# SolderDispenser_v1_2.net
KiCad netlist of a schematic drawn in EAGLE
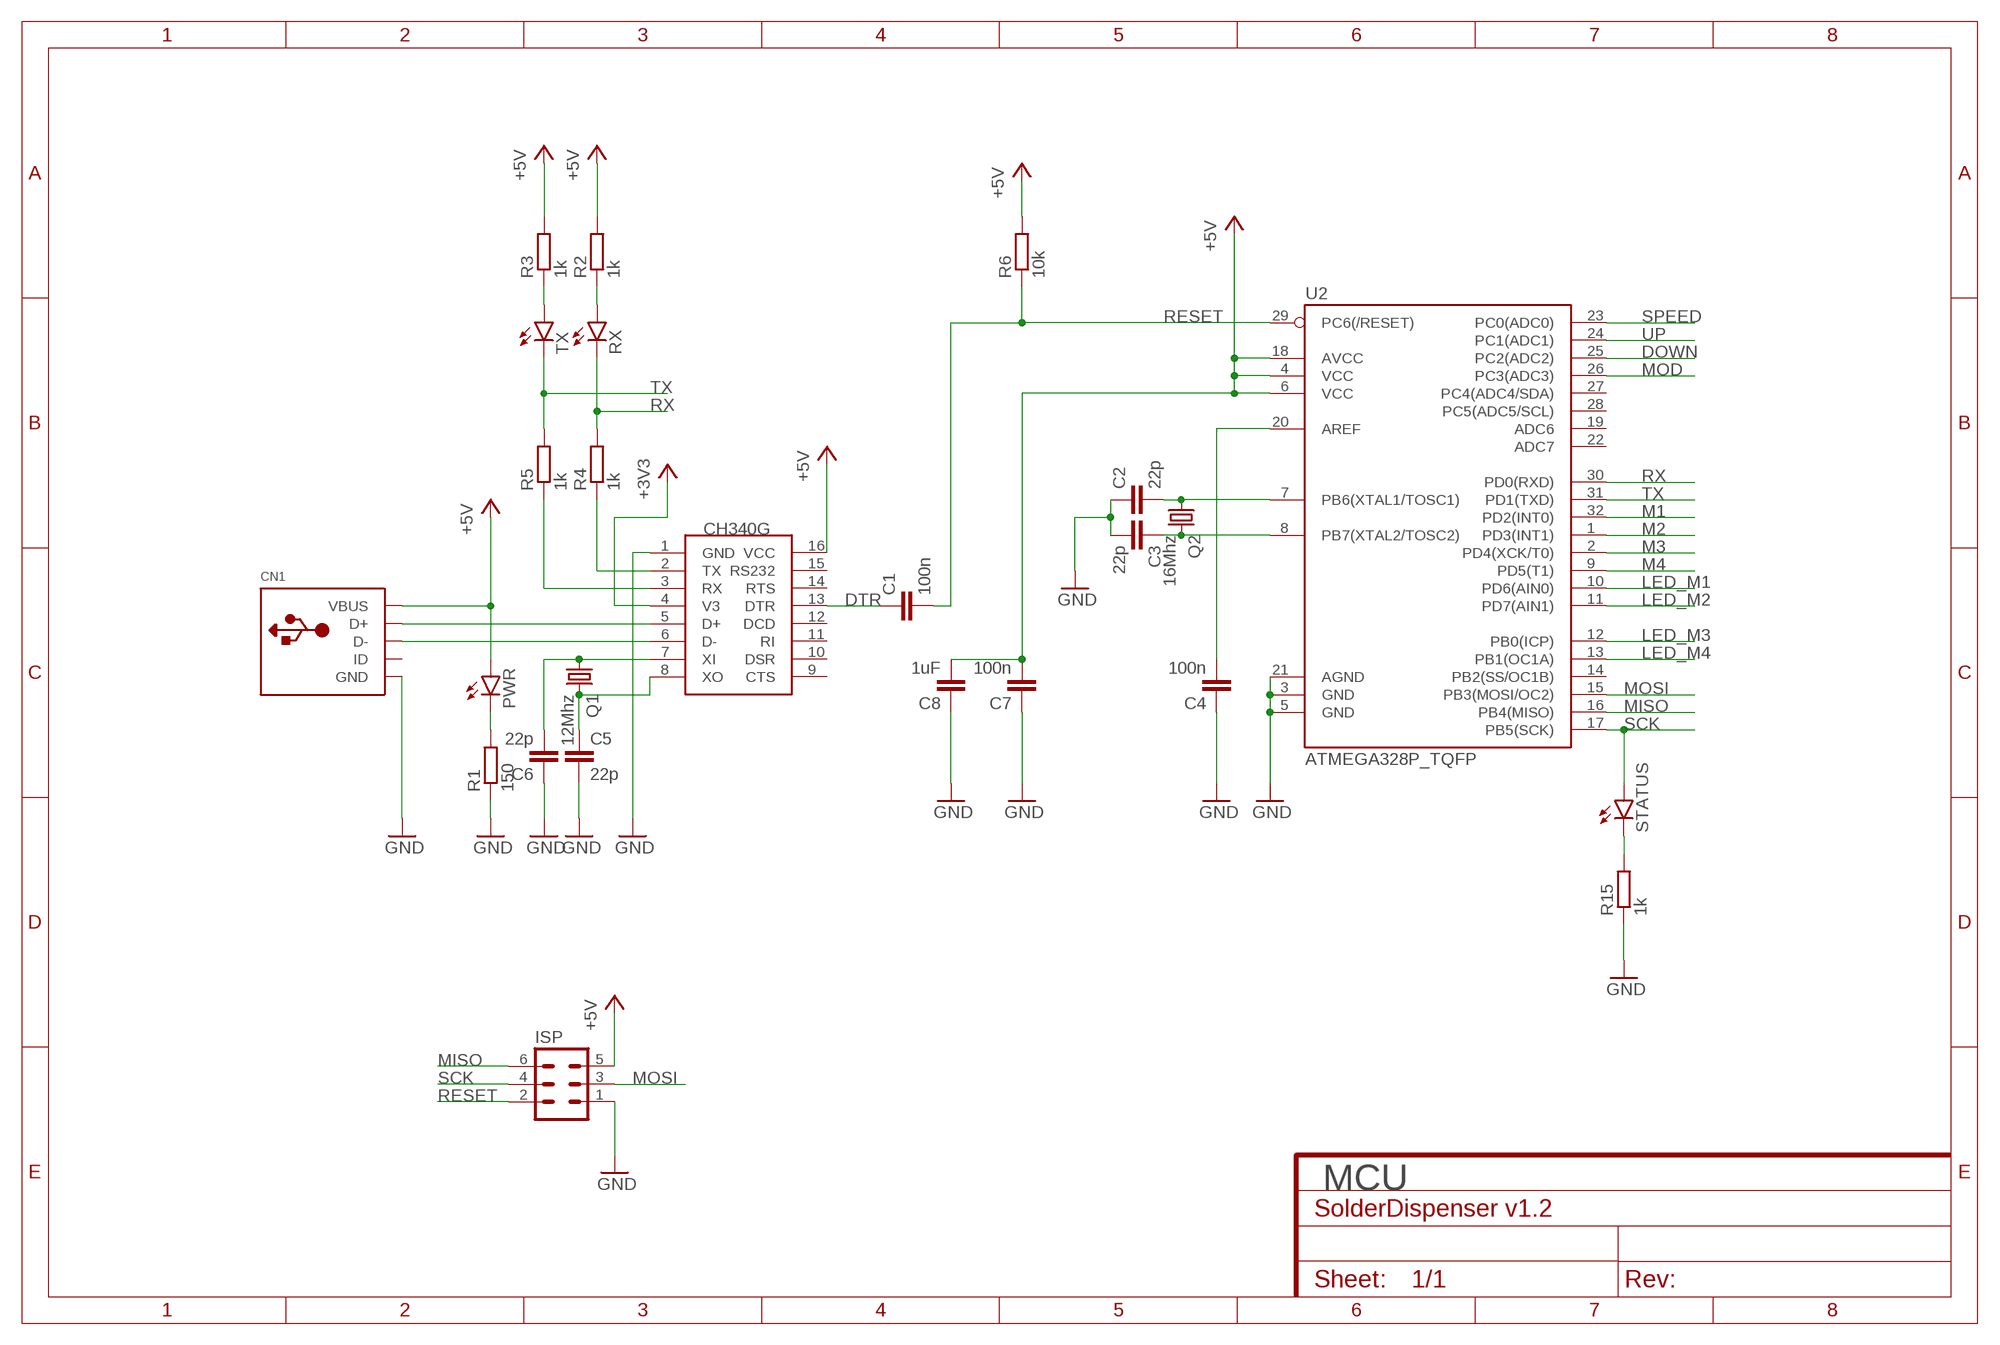
[diagram p0: schematic, sheet 1, part 1 of 2]
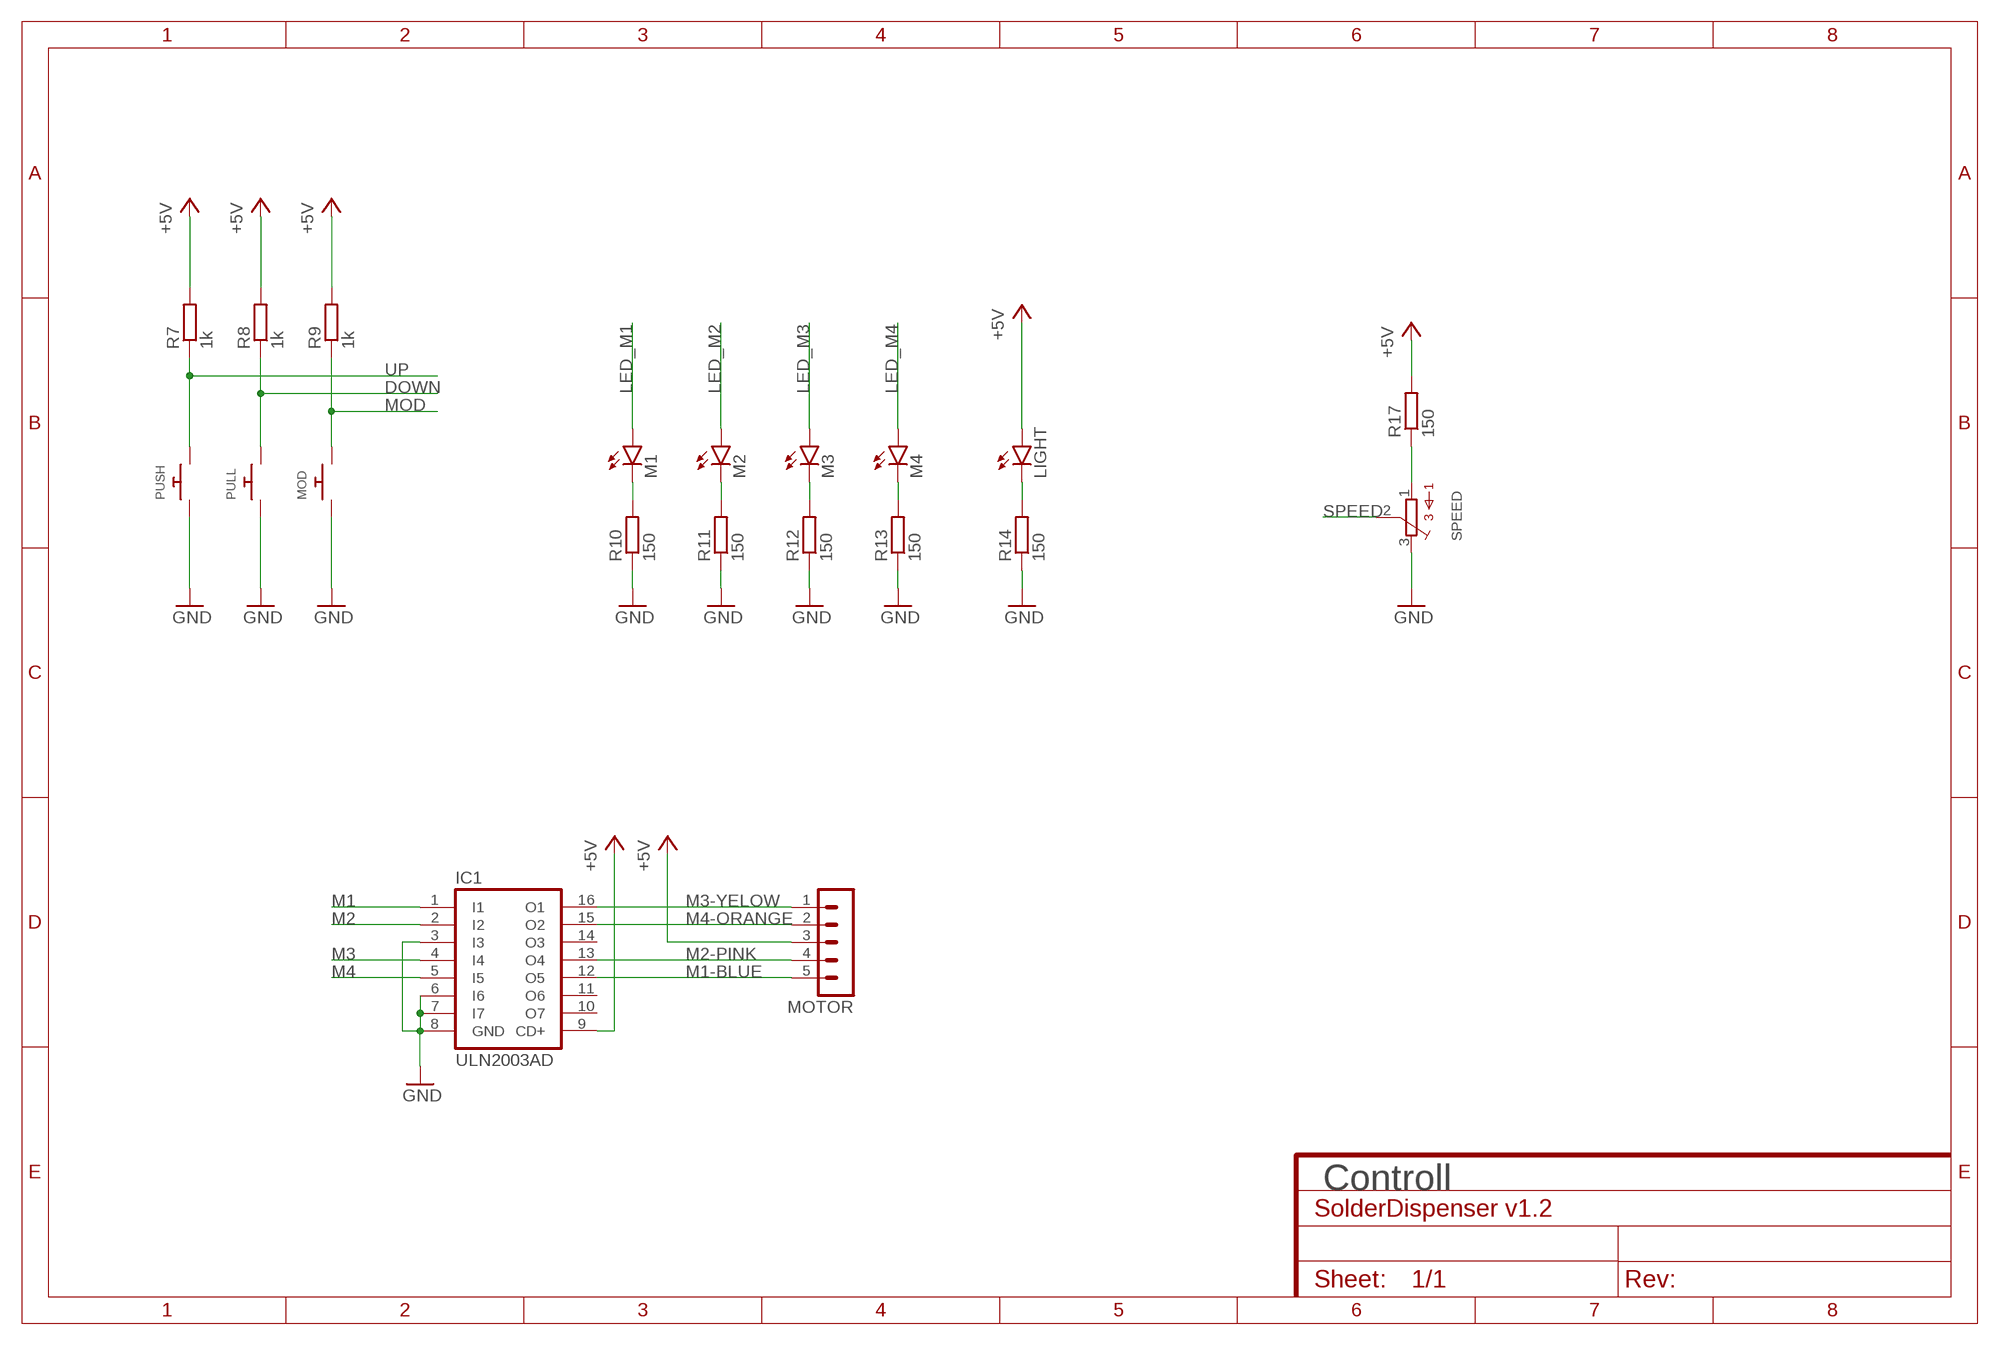
[diagram p1: schematic, sheet 1, part 2 of 2]

(export (version "E")
  (design (tool "Eeschema 10.0.6"))
  (components
    (comp (ref "C1")
      (value "100n")
      (footprint "eagle-import:C0805")
      (libsource (lib "eagle-import") (part "C-EUC0805"))
    )
    (comp (ref "C2")
      (value "22p")
      (footprint "eagle-import:C0805")
      (libsource (lib "eagle-import") (part "C-EUC0805"))
    )
    (comp (ref "C3")
      (value "22p")
      (footprint "eagle-import:C0805")
      (libsource (lib "eagle-import") (part "C-EUC0805"))
    )
    (comp (ref "C4")
      (value "100n")
      (footprint "eagle-import:C0805")
      (libsource (lib "eagle-import") (part "C-EUC0805"))
    )
    (comp (ref "C5")
      (value "22p")
      (footprint "eagle-import:C0805")
      (libsource (lib "eagle-import") (part "C-EUC0805"))
    )
    (comp (ref "C6")
      (value "22p")
      (footprint "eagle-import:C0805")
      (libsource (lib "eagle-import") (part "C-EUC0805"))
    )
    (comp (ref "C7")
      (value "100n")
      (footprint "eagle-import:C0805")
      (libsource (lib "eagle-import") (part "C-EUC0805"))
    )
    (comp (ref "C8")
      (value "1uF")
      (footprint "eagle-import:C0805")
      (libsource (lib "eagle-import") (part "C-EUC0805"))
    )
    (comp (ref "CN1")
      (value "USBMOLEX")
      (footprint "eagle-import:USB-MINIB-THM-MOLEX")
      (libsource (lib "eagle-import") (part "USBMOLEX"))
    )
    (comp (ref "IC1")
      (value "ULN2003AD")
      (footprint "eagle-import:SO16")
      (libsource (lib "eagle-import") (part "ULN2003AD"))
    )
    (comp (ref "ISP")
      (value "MA03-2")
      (footprint "eagle-import:MA03-2")
      (libsource (lib "eagle-import") (part "MA03-2"))
    )
    (comp (ref "LIGHT")
      (value "LED5MM")
      (footprint "eagle-import:LED5MM")
      (libsource (lib "eagle-import") (part "LED5MM"))
    )
    (comp (ref "M1")
      (value "LEDSML0805")
      (footprint "eagle-import:SML0805")
      (libsource (lib "eagle-import") (part "LEDSML0805"))
    )
    (comp (ref "M2")
      (value "LEDSML0805")
      (footprint "eagle-import:SML0805")
      (libsource (lib "eagle-import") (part "LEDSML0805"))
    )
    (comp (ref "M3")
      (value "LEDSML0805")
      (footprint "eagle-import:SML0805")
      (libsource (lib "eagle-import") (part "LEDSML0805"))
    )
    (comp (ref "M4")
      (value "LEDSML0805")
      (footprint "eagle-import:SML0805")
      (libsource (lib "eagle-import") (part "LEDSML0805"))
    )
    (comp (ref "MOD")
      (value "SWITCH_PUSHBUTTONEVQ-PE")
      (footprint "eagle-import:TACT_PANA-EVQ")
      (libsource (lib "eagle-import") (part "SWITCH_PUSHBUTTONEVQ-PE"))
    )
    (comp (ref "MOTOR")
      (value "MA05-1")
      (footprint "eagle-import:MA05-1")
      (libsource (lib "eagle-import") (part "MA05-1"))
    )
    (comp (ref "PULL")
      (value "SWITCH_PUSHBUTTONEVQ-PE")
      (footprint "eagle-import:TACT_PANA-EVQ")
      (libsource (lib "eagle-import") (part "SWITCH_PUSHBUTTONEVQ-PE"))
    )
    (comp (ref "PUSH")
      (value "SWITCH_PUSHBUTTONEVQ-PE")
      (footprint "eagle-import:TACT_PANA-EVQ")
      (libsource (lib "eagle-import") (part "SWITCH_PUSHBUTTONEVQ-PE"))
    )
    (comp (ref "PWR")
      (value "LEDSML0805")
      (footprint "eagle-import:SML0805")
      (libsource (lib "eagle-import") (part "LEDSML0805"))
    )
    (comp (ref "Q1")
      (value "12Mhz")
      (footprint "eagle-import:HC49UP")
      (libsource (lib "eagle-import") (part "CRYSTALHC49UP"))
    )
    (comp (ref "Q2")
      (value "16Mhz")
      (footprint "eagle-import:HC49UP")
      (libsource (lib "eagle-import") (part "CRYSTALHC49UP"))
    )
    (comp (ref "R1")
      (value "150")
      (footprint "eagle-import:R0805")
      (libsource (lib "eagle-import") (part "R-EU_R0805"))
    )
    (comp (ref "R2")
      (value "1k")
      (footprint "eagle-import:R0805")
      (libsource (lib "eagle-import") (part "R-EU_R0805"))
    )
    (comp (ref "R3")
      (value "1k")
      (footprint "eagle-import:R0805")
      (libsource (lib "eagle-import") (part "R-EU_R0805"))
    )
    (comp (ref "R4")
      (value "1k")
      (footprint "eagle-import:R0805")
      (libsource (lib "eagle-import") (part "R-EU_R0805"))
    )
    (comp (ref "R5")
      (value "1k")
      (footprint "eagle-import:R0805")
      (libsource (lib "eagle-import") (part "R-EU_R0805"))
    )
    (comp (ref "R6")
      (value "10k")
      (footprint "eagle-import:R0805")
      (libsource (lib "eagle-import") (part "R-EU_R0805"))
    )
    (comp (ref "R7")
      (value "1k")
      (footprint "eagle-import:R0805")
      (libsource (lib "eagle-import") (part "R-EU_R0805"))
    )
    (comp (ref "R8")
      (value "1k")
      (footprint "eagle-import:R0805")
      (libsource (lib "eagle-import") (part "R-EU_R0805"))
    )
    (comp (ref "R9")
      (value "1k")
      (footprint "eagle-import:R0805")
      (libsource (lib "eagle-import") (part "R-EU_R0805"))
    )
    (comp (ref "R10")
      (value "150")
      (footprint "eagle-import:R0805")
      (libsource (lib "eagle-import") (part "R-EU_R0805"))
    )
    (comp (ref "R11")
      (value "150")
      (footprint "eagle-import:R0805")
      (libsource (lib "eagle-import") (part "R-EU_R0805"))
    )
    (comp (ref "R12")
      (value "150")
      (footprint "eagle-import:R0805")
      (libsource (lib "eagle-import") (part "R-EU_R0805"))
    )
    (comp (ref "R13")
      (value "150")
      (footprint "eagle-import:R0805")
      (libsource (lib "eagle-import") (part "R-EU_R0805"))
    )
    (comp (ref "R14")
      (value "150")
      (footprint "eagle-import:R0805")
      (libsource (lib "eagle-import") (part "R-EU_R0805"))
    )
    (comp (ref "R15")
      (value "1k")
      (footprint "eagle-import:R0805")
      (libsource (lib "eagle-import") (part "R-EU_R0805"))
    )
    (comp (ref "R17")
      (value "150")
      (footprint "eagle-import:R0805")
      (libsource (lib "eagle-import") (part "R-EU_R0805"))
    )
    (comp (ref "RX")
      (value "LEDSML0805")
      (footprint "eagle-import:SML0805")
      (libsource (lib "eagle-import") (part "LEDSML0805"))
    )
    (comp (ref "SPEED")
      (value "3362P")
      (footprint "eagle-import:3362P")
      (libsource (lib "eagle-import") (part "3362P"))
    )
    (comp (ref "STATUS")
      (value "LEDSML0805")
      (footprint "eagle-import:SML0805")
      (libsource (lib "eagle-import") (part "LEDSML0805"))
    )
    (comp (ref "TX")
      (value "LEDSML0805")
      (footprint "eagle-import:SML0805")
      (libsource (lib "eagle-import") (part "LEDSML0805"))
    )
    (comp (ref "U$1")
      (value "CH340G")
      (footprint "eagle-import:SOIC16")
      (libsource (lib "eagle-import") (part "CH340G"))
    )
    (comp (ref "U2")
      (value "ATMEGA328P_TQFP")
      (footprint "eagle-import:TQFP32-08")
      (libsource (lib "eagle-import") (part "ATMEGA328P_TQFP"))
    )
  )
  (nets
    (net (code "1") (name "+3V3") (class "Default")
      (node (ref "U$1") (pin "4") (pinfunction "V3_4") (pintype "bidirectional"))
    )
    (net (code "2") (name "+5V") (class "Default")
      (node (ref "C7") (pin "2") (pinfunction "2_2") (pintype "passive"))
      (node (ref "C8") (pin "2") (pinfunction "2_2") (pintype "passive"))
      (node (ref "CN1") (pin "VBUS") (pinfunction "VBUS_VBUS") (pintype "power_in"))
      (node (ref "IC1") (pin "9") (pinfunction "CD+_9") (pintype "passive"))
      (node (ref "ISP") (pin "5") (pinfunction "5_5") (pintype "passive"))
      (node (ref "LIGHT") (pin "A") (pinfunction "A_A") (pintype "passive"))
      (node (ref "MOTOR") (pin "3") (pinfunction "3_3") (pintype "passive"))
      (node (ref "PWR") (pin "A") (pinfunction "A_A") (pintype "passive"))
      (node (ref "R17") (pin "2") (pinfunction "2_2") (pintype "passive"))
      (node (ref "R2") (pin "2") (pinfunction "2_2") (pintype "passive"))
      (node (ref "R3") (pin "2") (pinfunction "2_2") (pintype "passive"))
      (node (ref "R6") (pin "2") (pinfunction "2_2") (pintype "passive"))
      (node (ref "R7") (pin "2") (pinfunction "2_2") (pintype "passive"))
      (node (ref "R8") (pin "2") (pinfunction "2_2") (pintype "passive"))
      (node (ref "R9") (pin "2") (pinfunction "2_2") (pintype "passive"))
      (node (ref "U$1") (pin "16") (pinfunction "VCC_16") (pintype "bidirectional"))
      (node (ref "U2") (pin "18") (pinfunction "AVCC_18") (pintype "bidirectional"))
      (node (ref "U2") (pin "4") (pinfunction "VCC_4") (pintype "bidirectional"))
      (node (ref "U2") (pin "6") (pinfunction "VCC_6") (pintype "bidirectional"))
    )
    (net (code "3") (name "/DOWN") (class "Default")
      (node (ref "PULL") (pin "P$2") (pinfunction "P$2_P$2") (pintype "passive"))
      (node (ref "R8") (pin "1") (pinfunction "1_1") (pintype "passive"))
      (node (ref "U2") (pin "25") (pinfunction "PC2(ADC2)_25") (pintype "bidirectional"))
    )
    (net (code "4") (name "/DTR") (class "Default")
      (node (ref "C1") (pin "1") (pinfunction "1_1") (pintype "passive"))
      (node (ref "U$1") (pin "13") (pinfunction "DTR_13") (pintype "bidirectional"))
    )
    (net (code "5") (name "/LED_M1") (class "Default")
      (node (ref "M1") (pin "A") (pinfunction "A_A") (pintype "passive"))
      (node (ref "U2") (pin "10") (pinfunction "PD6(AIN0)_10") (pintype "bidirectional"))
    )
    (net (code "6") (name "/LED_M2") (class "Default")
      (node (ref "M2") (pin "A") (pinfunction "A_A") (pintype "passive"))
      (node (ref "U2") (pin "11") (pinfunction "PD7(AIN1)_11") (pintype "bidirectional"))
    )
    (net (code "7") (name "/LED_M3") (class "Default")
      (node (ref "M3") (pin "A") (pinfunction "A_A") (pintype "passive"))
      (node (ref "U2") (pin "12") (pinfunction "PB0(ICP)_12") (pintype "bidirectional"))
    )
    (net (code "8") (name "/LED_M4") (class "Default")
      (node (ref "M4") (pin "A") (pinfunction "A_A") (pintype "passive"))
      (node (ref "U2") (pin "13") (pinfunction "PB1(OC1A)_13") (pintype "bidirectional"))
    )
    (net (code "9") (name "/M1") (class "Default")
      (node (ref "IC1") (pin "1") (pinfunction "I1_1") (pintype "input"))
      (node (ref "U2") (pin "32") (pinfunction "PD2(INT0)_32") (pintype "bidirectional"))
    )
    (net (code "10") (name "/M1-BLUE") (class "Default")
      (node (ref "IC1") (pin "12") (pinfunction "O5_12") (pintype "open_collector"))
      (node (ref "MOTOR") (pin "5") (pinfunction "5_5") (pintype "passive"))
    )
    (net (code "11") (name "/M2") (class "Default")
      (node (ref "IC1") (pin "2") (pinfunction "I2_2") (pintype "input"))
      (node (ref "U2") (pin "1") (pinfunction "PD3(INT1)_1") (pintype "bidirectional"))
    )
    (net (code "12") (name "/M2-PINK") (class "Default")
      (node (ref "IC1") (pin "13") (pinfunction "O4_13") (pintype "open_collector"))
      (node (ref "MOTOR") (pin "4") (pinfunction "4_4") (pintype "passive"))
    )
    (net (code "13") (name "/M3") (class "Default")
      (node (ref "IC1") (pin "4") (pinfunction "I4_4") (pintype "input"))
      (node (ref "U2") (pin "2") (pinfunction "PD4(XCK/T0)_2") (pintype "bidirectional"))
    )
    (net (code "14") (name "/M3-YELOW") (class "Default")
      (node (ref "IC1") (pin "16") (pinfunction "O1_16") (pintype "open_collector"))
      (node (ref "MOTOR") (pin "1") (pinfunction "1_1") (pintype "passive"))
    )
    (net (code "15") (name "/M4") (class "Default")
      (node (ref "IC1") (pin "5") (pinfunction "I5_5") (pintype "input"))
      (node (ref "U2") (pin "9") (pinfunction "PD5(T1)_9") (pintype "bidirectional"))
    )
    (net (code "16") (name "/M4-ORANGE") (class "Default")
      (node (ref "IC1") (pin "15") (pinfunction "O2_15") (pintype "open_collector"))
      (node (ref "MOTOR") (pin "2") (pinfunction "2_2") (pintype "passive"))
    )
    (net (code "17") (name "/MISO") (class "Default")
      (node (ref "ISP") (pin "6") (pinfunction "6_6") (pintype "passive"))
      (node (ref "U2") (pin "16") (pinfunction "PB4(MISO)_16") (pintype "bidirectional"))
    )
    (net (code "18") (name "/MOD") (class "Default")
      (node (ref "MOD") (pin "P$2") (pinfunction "P$2_P$2") (pintype "passive"))
      (node (ref "R9") (pin "1") (pinfunction "1_1") (pintype "passive"))
      (node (ref "U2") (pin "26") (pinfunction "PC3(ADC3)_26") (pintype "bidirectional"))
    )
    (net (code "19") (name "/MOSI") (class "Default")
      (node (ref "ISP") (pin "3") (pinfunction "3_3") (pintype "passive"))
      (node (ref "U2") (pin "15") (pinfunction "PB3(MOSI/OC2)_15") (pintype "bidirectional"))
    )
    (net (code "20") (name "/RESET") (class "Default")
      (node (ref "C1") (pin "2") (pinfunction "2_2") (pintype "passive"))
      (node (ref "ISP") (pin "2") (pinfunction "2_2") (pintype "passive"))
      (node (ref "R6") (pin "1") (pinfunction "1_1") (pintype "passive"))
      (node (ref "U2") (pin "29") (pinfunction "PC6(/RESET)_29") (pintype "bidirectional"))
    )
    (net (code "21") (name "/RX") (class "Default")
      (node (ref "R4") (pin "2") (pinfunction "2_2") (pintype "passive"))
      (node (ref "RX") (pin "C") (pinfunction "C_C") (pintype "passive"))
      (node (ref "U2") (pin "30") (pinfunction "PD0(RXD)_30") (pintype "bidirectional"))
    )
    (net (code "22") (name "/SCK") (class "Default")
      (node (ref "ISP") (pin "4") (pinfunction "4_4") (pintype "passive"))
      (node (ref "STATUS") (pin "A") (pinfunction "A_A") (pintype "passive"))
      (node (ref "U2") (pin "17") (pinfunction "PB5(SCK)_17") (pintype "bidirectional"))
    )
    (net (code "23") (name "/SPEED") (class "Default")
      (node (ref "SPEED") (pin "2") (pinfunction "2_2") (pintype "passive"))
      (node (ref "U2") (pin "23") (pinfunction "PC0(ADC0)_23") (pintype "bidirectional"))
    )
    (net (code "24") (name "/TX") (class "Default")
      (node (ref "R5") (pin "2") (pinfunction "2_2") (pintype "passive"))
      (node (ref "TX") (pin "C") (pinfunction "C_C") (pintype "passive"))
      (node (ref "U2") (pin "31") (pinfunction "PD1(TXD)_31") (pintype "bidirectional"))
    )
    (net (code "25") (name "/UP") (class "Default")
      (node (ref "PUSH") (pin "P$2") (pinfunction "P$2_P$2") (pintype "passive"))
      (node (ref "R7") (pin "1") (pinfunction "1_1") (pintype "passive"))
      (node (ref "U2") (pin "24") (pinfunction "PC1(ADC1)_24") (pintype "bidirectional"))
    )
    (net (code "26") (name "GND") (class "Default")
      (node (ref "C2") (pin "1") (pinfunction "1_1") (pintype "passive"))
      (node (ref "C3") (pin "2") (pinfunction "2_2") (pintype "passive"))
      (node (ref "C4") (pin "1") (pinfunction "1_1") (pintype "passive"))
      (node (ref "C5") (pin "2") (pinfunction "2_2") (pintype "passive"))
      (node (ref "C6") (pin "1") (pinfunction "1_1") (pintype "passive"))
      (node (ref "C7") (pin "1") (pinfunction "1_1") (pintype "passive"))
      (node (ref "C8") (pin "1") (pinfunction "1_1") (pintype "passive"))
      (node (ref "CN1") (pin "GND") (pinfunction "GND_GND") (pintype "power_in"))
      (node (ref "IC1") (pin "3") (pinfunction "I3_3") (pintype "input"))
      (node (ref "IC1") (pin "6") (pinfunction "I6_6") (pintype "input"))
      (node (ref "IC1") (pin "7") (pinfunction "I7_7") (pintype "input"))
      (node (ref "IC1") (pin "8") (pinfunction "GND_8") (pintype "power_in"))
      (node (ref "ISP") (pin "1") (pinfunction "1_1") (pintype "passive"))
      (node (ref "MOD") (pin "P$1") (pinfunction "P$1_P$1") (pintype "passive"))
      (node (ref "PULL") (pin "P$1") (pinfunction "P$1_P$1") (pintype "passive"))
      (node (ref "PUSH") (pin "P$1") (pinfunction "P$1_P$1") (pintype "passive"))
      (node (ref "R1") (pin "1") (pinfunction "1_1") (pintype "passive"))
      (node (ref "R10") (pin "1") (pinfunction "1_1") (pintype "passive"))
      (node (ref "R11") (pin "1") (pinfunction "1_1") (pintype "passive"))
      (node (ref "R12") (pin "1") (pinfunction "1_1") (pintype "passive"))
      (node (ref "R13") (pin "1") (pinfunction "1_1") (pintype "passive"))
      (node (ref "R14") (pin "1") (pinfunction "1_1") (pintype "passive"))
      (node (ref "R15") (pin "1") (pinfunction "1_1") (pintype "passive"))
      (node (ref "SPEED") (pin "3") (pinfunction "3_3") (pintype "passive"))
      (node (ref "U$1") (pin "1") (pinfunction "GND_1") (pintype "bidirectional"))
      (node (ref "U2") (pin "21") (pinfunction "AGND_21") (pintype "bidirectional"))
      (node (ref "U2") (pin "3") (pinfunction "GND_3") (pintype "bidirectional"))
      (node (ref "U2") (pin "5") (pinfunction "GND_5") (pintype "bidirectional"))
    )
    (net (code "27") (name "Net-(LIGHT-C)") (class "Default")
      (node (ref "LIGHT") (pin "K") (pinfunction "C_K") (pintype "passive"))
      (node (ref "R14") (pin "2") (pinfunction "2_2") (pintype "passive"))
    )
    (net (code "28") (name "Net-(M1-PadC)") (class "Default")
      (node (ref "M1") (pin "C") (pinfunction "C_C") (pintype "passive"))
      (node (ref "R10") (pin "2") (pinfunction "2_2") (pintype "passive"))
    )
    (net (code "29") (name "Net-(M2-PadC)") (class "Default")
      (node (ref "M2") (pin "C") (pinfunction "C_C") (pintype "passive"))
      (node (ref "R11") (pin "2") (pinfunction "2_2") (pintype "passive"))
    )
    (net (code "30") (name "Net-(M3-PadC)") (class "Default")
      (node (ref "M3") (pin "C") (pinfunction "C_C") (pintype "passive"))
      (node (ref "R12") (pin "2") (pinfunction "2_2") (pintype "passive"))
    )
    (net (code "31") (name "Net-(M4-PadC)") (class "Default")
      (node (ref "M4") (pin "C") (pinfunction "C_C") (pintype "passive"))
      (node (ref "R13") (pin "2") (pinfunction "2_2") (pintype "passive"))
    )
    (net (code "32") (name "Net-(PWR-PadC)") (class "Default")
      (node (ref "PWR") (pin "C") (pinfunction "C_C") (pintype "passive"))
      (node (ref "R1") (pin "2") (pinfunction "2_2") (pintype "passive"))
    )
    (net (code "33") (name "Net-(R2-Pad1)") (class "Default")
      (node (ref "R2") (pin "1") (pinfunction "1_1") (pintype "passive"))
      (node (ref "RX") (pin "A") (pinfunction "A_A") (pintype "passive"))
    )
    (net (code "34") (name "Net-(R3-Pad1)") (class "Default")
      (node (ref "R3") (pin "1") (pinfunction "1_1") (pintype "passive"))
      (node (ref "TX") (pin "A") (pinfunction "A_A") (pintype "passive"))
    )
    (net (code "35") (name "Net-(R15-Pad2)") (class "Default")
      (node (ref "R15") (pin "2") (pinfunction "2_2") (pintype "passive"))
      (node (ref "STATUS") (pin "C") (pinfunction "C_C") (pintype "passive"))
    )
    (net (code "36") (name "Net-(R17-Pad1)") (class "Default")
      (node (ref "R17") (pin "1") (pinfunction "1_1") (pintype "passive"))
      (node (ref "SPEED") (pin "1") (pinfunction "1_1") (pintype "passive"))
    )
    (net (code "37") (name "Net-(U$1-D+)") (class "Default")
      (node (ref "CN1") (pin "D+") (pinfunction "D+_D+") (pintype "bidirectional"))
      (node (ref "U$1") (pin "5") (pinfunction "D+_5") (pintype "bidirectional"))
    )
    (net (code "38") (name "Net-(U$1-D-)") (class "Default")
      (node (ref "CN1") (pin "D-") (pinfunction "D-_D-") (pintype "bidirectional"))
      (node (ref "U$1") (pin "6") (pinfunction "D-_6") (pintype "bidirectional"))
    )
    (net (code "39") (name "Net-(U$1-RX)") (class "Default")
      (node (ref "R5") (pin "1") (pinfunction "1_1") (pintype "passive"))
      (node (ref "U$1") (pin "3") (pinfunction "RX_3") (pintype "bidirectional"))
    )
    (net (code "40") (name "Net-(U$1-TX)") (class "Default")
      (node (ref "R4") (pin "1") (pinfunction "1_1") (pintype "passive"))
      (node (ref "U$1") (pin "2") (pinfunction "TX_2") (pintype "bidirectional"))
    )
    (net (code "41") (name "Net-(U$1-XI)") (class "Default")
      (node (ref "C6") (pin "2") (pinfunction "2_2") (pintype "passive"))
      (node (ref "Q1") (pin "1") (pinfunction "1_1") (pintype "passive"))
      (node (ref "U$1") (pin "7") (pinfunction "XI_7") (pintype "bidirectional"))
    )
    (net (code "42") (name "Net-(U$1-XO)") (class "Default")
      (node (ref "C5") (pin "1") (pinfunction "1_1") (pintype "passive"))
      (node (ref "Q1") (pin "2") (pinfunction "2_2") (pintype "passive"))
      (node (ref "U$1") (pin "8") (pinfunction "XO_8") (pintype "bidirectional"))
    )
    (net (code "43") (name "Net-(U2-AREF)") (class "Default")
      (node (ref "C4") (pin "2") (pinfunction "2_2") (pintype "passive"))
      (node (ref "U2") (pin "20") (pinfunction "AREF_20") (pintype "bidirectional"))
    )
    (net (code "44") (name "Net-(U2-PB6(XTAL1{slash}TOSC1))") (class "Default")
      (node (ref "C2") (pin "2") (pinfunction "2_2") (pintype "passive"))
      (node (ref "Q2") (pin "1") (pinfunction "1_1") (pintype "passive"))
      (node (ref "U2") (pin "7") (pinfunction "PB6(XTAL1/TOSC1)_7") (pintype "bidirectional"))
    )
    (net (code "45") (name "Net-(U2-PB7(XTAL2{slash}TOSC2))") (class "Default")
      (node (ref "C3") (pin "1") (pinfunction "1_1") (pintype "passive"))
      (node (ref "Q2") (pin "2") (pinfunction "2_2") (pintype "passive"))
      (node (ref "U2") (pin "8") (pinfunction "PB7(XTAL2/TOSC2)_8") (pintype "bidirectional"))
    )
    (net (code "46") (name "unconnected-(CN1-PadID)") (class "Default")
      (node (ref "CN1") (pin "ID") (pinfunction "ID_ID") (pintype "bidirectional"))
    )
    (net (code "47") (name "unconnected-(IC1-O3-Pad14)") (class "Default")
      (node (ref "IC1") (pin "14") (pinfunction "O3_14") (pintype "open_collector"))
    )
    (net (code "48") (name "unconnected-(IC1-O6-Pad11)") (class "Default")
      (node (ref "IC1") (pin "11") (pinfunction "O6_11") (pintype "open_collector"))
    )
    (net (code "49") (name "unconnected-(IC1-O7-Pad10)") (class "Default")
      (node (ref "IC1") (pin "10") (pinfunction "O7_10") (pintype "open_collector"))
    )
    (net (code "50") (name "unconnected-(U$1-CTS-Pad9)") (class "Default")
      (node (ref "U$1") (pin "9") (pinfunction "CTS_9") (pintype "bidirectional"))
    )
    (net (code "51") (name "unconnected-(U$1-DCD-Pad12)") (class "Default")
      (node (ref "U$1") (pin "12") (pinfunction "DCD_12") (pintype "bidirectional"))
    )
    (net (code "52") (name "unconnected-(U$1-DSR-Pad10)") (class "Default")
      (node (ref "U$1") (pin "10") (pinfunction "DSR_10") (pintype "bidirectional"))
    )
    (net (code "53") (name "unconnected-(U$1-RI-Pad11)") (class "Default")
      (node (ref "U$1") (pin "11") (pinfunction "RI_11") (pintype "bidirectional"))
    )
    (net (code "54") (name "unconnected-(U$1-RS232-Pad15)") (class "Default")
      (node (ref "U$1") (pin "15") (pinfunction "RS232_15") (pintype "bidirectional"))
    )
    (net (code "55") (name "unconnected-(U$1-RTS-Pad14)") (class "Default")
      (node (ref "U$1") (pin "14") (pinfunction "RTS_14") (pintype "bidirectional"))
    )
    (net (code "56") (name "unconnected-(U2-ADC6-Pad19)") (class "Default")
      (node (ref "U2") (pin "19") (pinfunction "ADC6_19") (pintype "bidirectional"))
    )
    (net (code "57") (name "unconnected-(U2-ADC7-Pad22)") (class "Default")
      (node (ref "U2") (pin "22") (pinfunction "ADC7_22") (pintype "bidirectional"))
    )
    (net (code "58") (name "unconnected-(U2-PB2(SS{slash}OC1B)-Pad14)") (class "Default")
      (node (ref "U2") (pin "14") (pinfunction "PB2(SS/OC1B)_14") (pintype "bidirectional"))
    )
    (net (code "59") (name "unconnected-(U2-PC4(ADC4{slash}SDA)-Pad27)") (class "Default")
      (node (ref "U2") (pin "27") (pinfunction "PC4(ADC4/SDA)_27") (pintype "bidirectional"))
    )
    (net (code "60") (name "unconnected-(U2-PC5(ADC5{slash}SCL)-Pad28)") (class "Default")
      (node (ref "U2") (pin "28") (pinfunction "PC5(ADC5/SCL)_28") (pintype "bidirectional"))
    )
  )
)
